# Power_21_04_33.net
KiCad netlist of a schematic drawn in Altium Designer
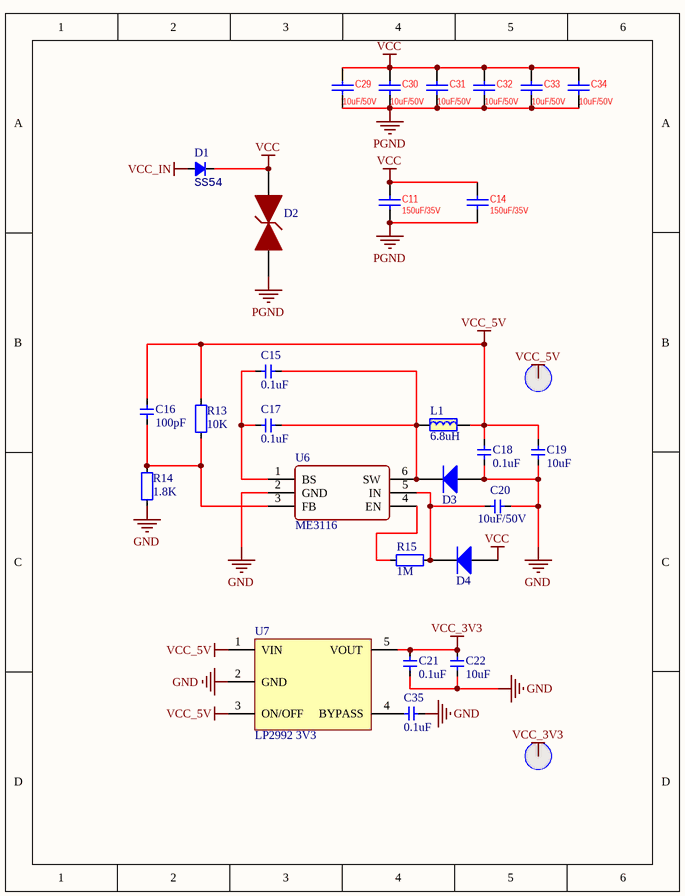
[diagram p0: Power 21.04.33.SchDoc]

(export (version "E")
  (design (tool "Eeschema 10.0.6"))
  (components
    (comp (ref "C11")
      (value "150uF/35V")
      (footprint "CAP-SMD_BD8.0-L8.3-W8.3-LS9.3-FD")
      (description "Capacitor, chip, ceramic")
      (fields (field (name "Comment") "220uF/25V"))
      (libsource (lib "OAKUSBFXS") (part "CAP"))
    )
    (comp (ref "C14")
      (value "150uF/35V")
      (footprint "CAP-SMD_BD8.0-L8.3-W8.3-LS9.3-FD")
      (description "Capacitor, chip, ceramic")
      (fields (field (name "Comment") "220uF/25V"))
      (libsource (lib "OAKUSBFXS") (part "CAP"))
    )
    (comp (ref "C15")
      (value "0.1uF")
      (footprint "motor42-lib:CAP_0402")
      (description "Capacitor")
      (libsource (lib "MyPcbLib") (part "电容-0402"))
    )
    (comp (ref "C16")
      (value "100pF")
      (footprint "CAP_0402")
      (description "Capacitor")
      (libsource (lib "MyPcbLib") (part "电容-0402"))
    )
    (comp (ref "C17")
      (value "0.1uF")
      (footprint "motor42-lib:CAP_0402")
      (description "Capacitor")
      (libsource (lib "MyPcbLib") (part "电容-0402"))
    )
    (comp (ref "C18")
      (value "0.1uF")
      (footprint "motor42-lib:CAP_0402")
      (description "Capacitor")
      (libsource (lib "MyPcbLib") (part "电容-0402"))
    )
    (comp (ref "C19")
      (value "10uF")
      (footprint "CAP_0402")
      (description "Capacitor")
      (libsource (lib "MyPcbLib") (part "电容-0402"))
    )
    (comp (ref "C20")
      (value "10uF/50V")
      (footprint "1206-CAP")
      (description "Capacitor")
      (libsource (lib "MyPcbLib") (part "电容-0402"))
    )
    (comp (ref "C21")
      (value "0.1uF")
      (footprint "motor42-lib:CAP_0402")
      (description "Capacitor")
      (libsource (lib "MyPcbLib") (part "电容-0402"))
    )
    (comp (ref "C22")
      (value "10uF")
      (footprint "CAP_0402")
      (description "Capacitor")
      (libsource (lib "MyPcbLib") (part "电容-0402"))
    )
    (comp (ref "C29")
      (value "10uF/50V")
      (footprint "1206-CAP")
      (description "Capacitor, chip, ceramic")
      (libsource (lib "OAKUSBFXS") (part "CAP"))
    )
    (comp (ref "C30")
      (value "10uF/50V")
      (footprint "1206-CAP")
      (description "Capacitor, chip, ceramic")
      (libsource (lib "OAKUSBFXS") (part "CAP"))
    )
    (comp (ref "C31")
      (value "10uF/50V")
      (footprint "1206-CAP")
      (description "Capacitor, chip, ceramic")
      (libsource (lib "OAKUSBFXS") (part "CAP"))
    )
    (comp (ref "C32")
      (value "10uF/50V")
      (footprint "1206-CAP")
      (description "Capacitor, chip, ceramic")
      (libsource (lib "OAKUSBFXS") (part "CAP"))
    )
    (comp (ref "C33")
      (value "10uF/50V")
      (footprint "1206-CAP")
      (description "Capacitor, chip, ceramic")
      (libsource (lib "OAKUSBFXS") (part "CAP"))
    )
    (comp (ref "C34")
      (value "10uF/50V")
      (footprint "1206-CAP")
      (description "Capacitor, chip, ceramic")
      (libsource (lib "OAKUSBFXS") (part "CAP"))
    )
    (comp (ref "C35")
      (value "0.1uF")
      (footprint "motor42-lib:CAP_0402")
      (description "Capacitor")
      (libsource (lib "MyPcbLib") (part "电容-0402"))
    )
    (comp (ref "D1")
      (value "SS54")
      (footprint "DO-214AC")
      (description "Diode")
      (libsource (lib "KitSprout") (part "Diode_SMA"))
    )
    (comp (ref "D2")
      (value "SMBJ28CA")
      (footprint "SMBJ-CA_MFG")
      (libsource (lib "MyPcbLib") (part "SMBJ28CA"))
    )
    (comp (ref "D3")
      (value "二极管-5819W")
      (footprint "SOD-323")
      (description "40V")
      (libsource (lib "MyPcbLib") (part "二极管-5819W"))
    )
    (comp (ref "D4")
      (value "二极管-5819W")
      (footprint "SOD-323")
      (description "40V")
      (libsource (lib "MyPcbLib") (part "二极管-5819W"))
    )
    (comp (ref "L1") (value "6.8uH") (footprint "IND-201612") (libsource (lib "MyPcbLib") (part "电感-201612")))
    (comp (ref "R13")
      (value "10K")
      (footprint "RES_0402")
      (description "Resistor")
      (libsource (lib "MyPcbLib") (part "电阻-0402"))
    )
    (comp (ref "R14")
      (value "1.8K")
      (footprint "RES_0402")
      (description "Resistor")
      (libsource (lib "MyPcbLib") (part "电阻-0402"))
    )
    (comp (ref "R15")
      (value "1M")
      (footprint "RES_0402")
      (description "Resistor")
      (libsource (lib "") (part "电阻-0402_1"))
    )
    (comp (ref "T1") (value "测试点") (footprint "TEST_PT") (libsource (lib "MyPcbLib") (part "测试点")))
    (comp (ref "T2") (value "测试点") (footprint "TEST_PT") (libsource (lib "MyPcbLib") (part "测试点")))
    (comp (ref "U6")
      (value "ME3116")
      (footprint "SOT23-6")
      (description "DC-DC")
      (libsource (lib "MyPcbLib") (part "ME3116"))
    )
    (comp (ref "U7")
      (value "LP2992 3V3")
      (footprint "SOT23-5")
      (description "LDO")
      (libsource (lib "MyPcbLib") (part "LP2992"))
    )
  )
  (nets
    (net (code "1") (name "GND") (class "Default")
      (node (ref "C18") (pin "1") (pinfunction "1_1") (pintype "passive"))
      (node (ref "C19") (pin "1") (pinfunction "1_1") (pintype "passive"))
      (node (ref "C20") (pin "1") (pinfunction "1_1") (pintype "passive"))
      (node (ref "C21") (pin "1") (pinfunction "1_1") (pintype "passive"))
      (node (ref "C22") (pin "1") (pinfunction "1_1") (pintype "passive"))
      (node (ref "C35") (pin "1") (pinfunction "1_1") (pintype "passive"))
      (node (ref "D3") (pin "1") (pinfunction "A_1") (pintype "passive"))
      (node (ref "R14") (pin "1") (pinfunction "1_1") (pintype "passive"))
      (node (ref "U6") (pin "2") (pinfunction "GND_2") (pintype "passive"))
      (node (ref "U7") (pin "2") (pinfunction "GND_2") (pintype "passive"))
    )
    (net (code "2") (name "Net-(D3-K)") (class "Default")
      (node (ref "C15") (pin "1") (pinfunction "1_1") (pintype "passive"))
      (node (ref "C17") (pin "1") (pinfunction "1_1") (pintype "passive"))
      (node (ref "D3") (pin "2") (pinfunction "K_2") (pintype "passive"))
      (node (ref "L1") (pin "1") (pintype "passive"))
      (node (ref "U6") (pin "6") (pinfunction "SW_6") (pintype "passive"))
    )
    (net (code "3") (name "Net-(D4-K)") (class "Default")
      (node (ref "C20") (pin "2") (pinfunction "2_2") (pintype "passive"))
      (node (ref "D4") (pin "2") (pinfunction "K_2") (pintype "passive"))
      (node (ref "R15") (pin "1") (pinfunction "1_1") (pintype "passive"))
      (node (ref "U6") (pin "5") (pinfunction "IN_5") (pintype "passive"))
    )
    (net (code "4") (name "Net-(U6-BS)") (class "Default")
      (node (ref "C15") (pin "2") (pinfunction "2_2") (pintype "passive"))
      (node (ref "C17") (pin "2") (pinfunction "2_2") (pintype "passive"))
      (node (ref "U6") (pin "1") (pinfunction "BS_1") (pintype "passive"))
    )
    (net (code "5") (name "Net-(U6-EN)") (class "Default")
      (node (ref "R15") (pin "2") (pinfunction "2_2") (pintype "passive"))
      (node (ref "U6") (pin "4") (pinfunction "EN_4") (pintype "passive"))
    )
    (net (code "6") (name "Net-(U6-FB)") (class "Default")
      (node (ref "C16") (pin "2") (pinfunction "2_2") (pintype "passive"))
      (node (ref "R13") (pin "1") (pinfunction "1_1") (pintype "passive"))
      (node (ref "R14") (pin "2") (pinfunction "2_2") (pintype "passive"))
      (node (ref "U6") (pin "3") (pinfunction "FB_3") (pintype "passive"))
    )
    (net (code "7") (name "Net-(U7-BYPASS)") (class "Default")
      (node (ref "C35") (pin "2") (pinfunction "2_2") (pintype "passive"))
      (node (ref "U7") (pin "4") (pinfunction "BYPASS_4") (pintype "passive"))
    )
    (net (code "8") (name "PGND") (class "Default")
      (node (ref "C11") (pin "2") (pinfunction "2_2") (pintype "passive"))
      (node (ref "C14") (pin "2") (pinfunction "2_2") (pintype "passive"))
      (node (ref "C29") (pin "2") (pinfunction "2_2") (pintype "passive"))
      (node (ref "C30") (pin "2") (pinfunction "2_2") (pintype "passive"))
      (node (ref "C31") (pin "2") (pinfunction "2_2") (pintype "passive"))
      (node (ref "C32") (pin "2") (pinfunction "2_2") (pintype "passive"))
      (node (ref "C33") (pin "2") (pinfunction "2_2") (pintype "passive"))
      (node (ref "C34") (pin "2") (pinfunction "2_2") (pintype "passive"))
      (node (ref "D2") (pin "1") (pinfunction "1_1") (pintype "passive"))
    )
    (net (code "9") (name "VCC") (class "Default")
      (node (ref "C11") (pin "1") (pinfunction "1_1") (pintype "passive"))
      (node (ref "C14") (pin "1") (pinfunction "1_1") (pintype "passive"))
      (node (ref "C29") (pin "1") (pinfunction "1_1") (pintype "passive"))
      (node (ref "C30") (pin "1") (pinfunction "1_1") (pintype "passive"))
      (node (ref "C31") (pin "1") (pinfunction "1_1") (pintype "passive"))
      (node (ref "C32") (pin "1") (pinfunction "1_1") (pintype "passive"))
      (node (ref "C33") (pin "1") (pinfunction "1_1") (pintype "passive"))
      (node (ref "C34") (pin "1") (pinfunction "1_1") (pintype "passive"))
      (node (ref "D1") (pin "2") (pinfunction "K_2") (pintype "passive"))
      (node (ref "D2") (pin "2") (pinfunction "2_2") (pintype "passive"))
      (node (ref "D4") (pin "1") (pinfunction "A_1") (pintype "passive"))
    )
    (net (code "10") (name "VCC_3V3") (class "Default")
      (node (ref "C21") (pin "2") (pinfunction "2_2") (pintype "passive"))
      (node (ref "C22") (pin "2") (pinfunction "2_2") (pintype "passive"))
      (node (ref "T2") (pin "0") (pinfunction "0_0") (pintype "passive"))
      (node (ref "U7") (pin "5") (pinfunction "VOUT_5") (pintype "passive"))
    )
    (net (code "11") (name "VCC_5V") (class "Default")
      (node (ref "C16") (pin "1") (pinfunction "1_1") (pintype "passive"))
      (node (ref "C18") (pin "2") (pinfunction "2_2") (pintype "passive"))
      (node (ref "C19") (pin "2") (pinfunction "2_2") (pintype "passive"))
      (node (ref "L1") (pin "2") (pinfunction "2_2") (pintype "passive"))
      (node (ref "R13") (pin "2") (pinfunction "2_2") (pintype "passive"))
      (node (ref "T1") (pin "0") (pinfunction "0_0") (pintype "passive"))
      (node (ref "U7") (pin "1") (pinfunction "VIN_1") (pintype "passive"))
      (node (ref "U7") (pin "3") (pinfunction "ON/OFF_3") (pintype "passive"))
    )
    (net (code "12") (name "VCC_IN") (class "Default")
      (node (ref "D1") (pin "1") (pinfunction "A_1") (pintype "passive"))
    )
  )
)
